# Power.net
KiCad netlist of a schematic drawn in Altium Designer
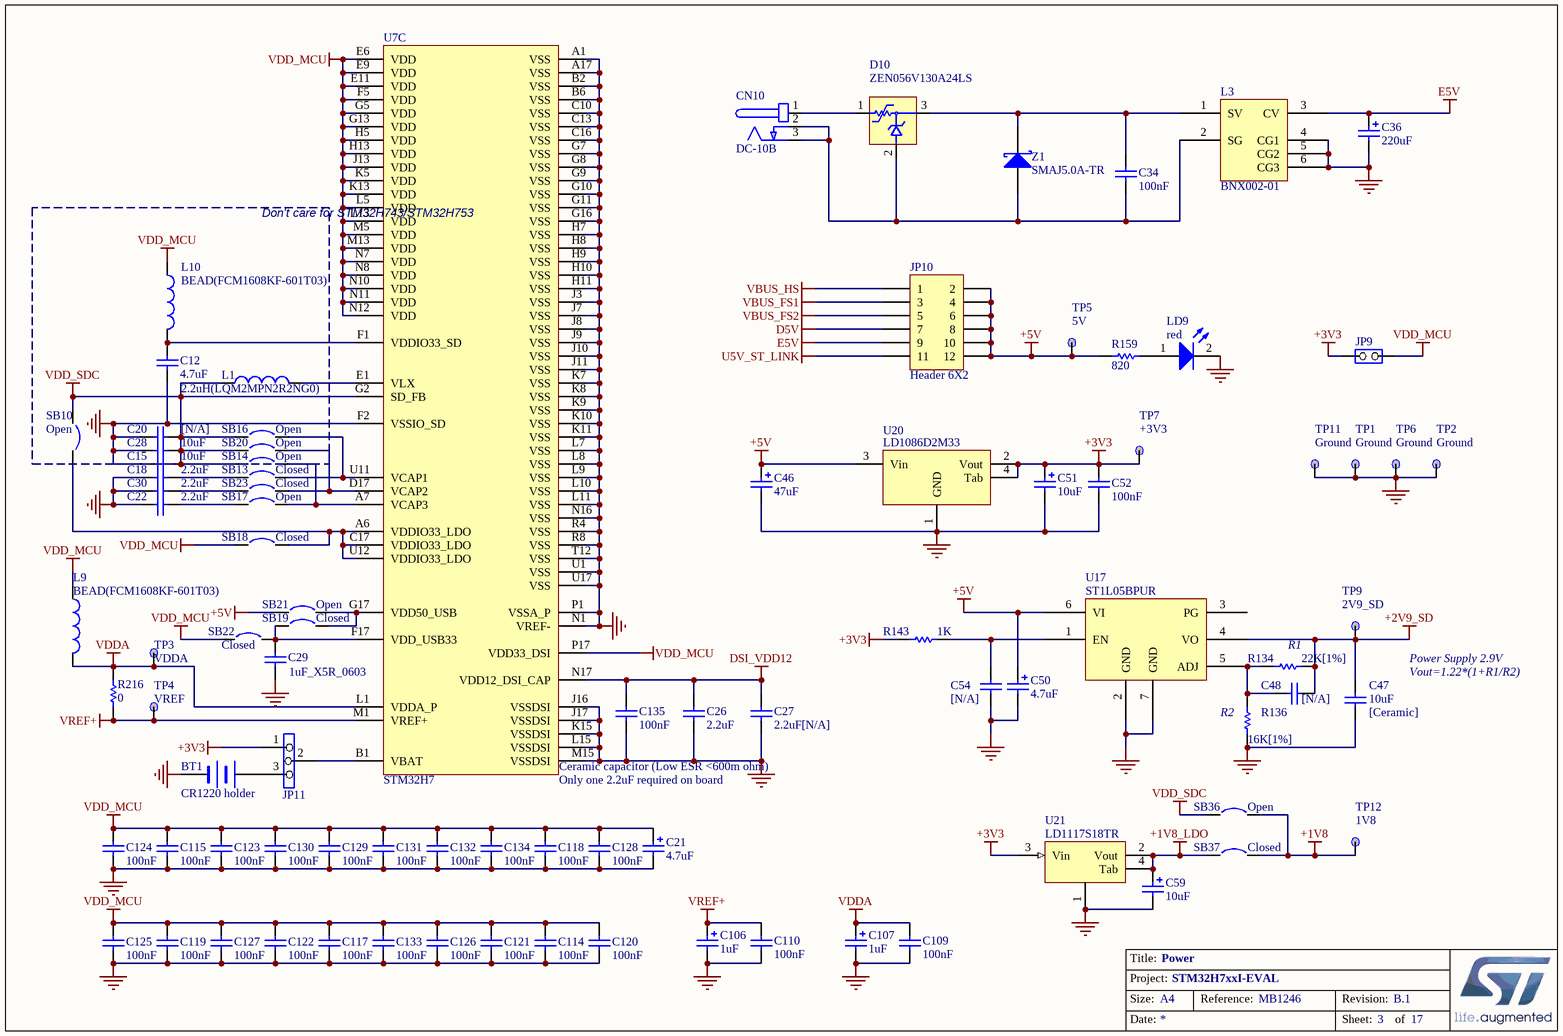
[diagram p0: Power.SchDoc]

(export (version "E")
  (design (tool "Eeschema 10.0.6"))
  (components
    (comp (ref "BT1")
      (value "CR1220 holder")
      (footprint "BAT_2SM_CR1220")
      (description "Battery")
      (libsource (lib "*") (part "BATTERY"))
    )
    (comp (ref "C12")
      (value "4.7uF")
      (footprint "0603C")
      (description "Capacitor")
      (fields (field (name "PUBLISHER") "Altium Limited"))
      (libsource (lib "Miscellaneous Devices") (part "Cap"))
    )
    (comp (ref "C15")
      (value "10uF")
      (footprint "0603C")
      (description "Capacitor")
      (fields (field (name "PUBLISHER") "Altium Limited"))
      (libsource (lib "Miscellaneous Devices") (part "Cap"))
    )
    (comp (ref "C18")
      (value "2.2uF")
      (footprint "0603C")
      (description "Capacitor")
      (fields (field (name "PUBLISHER") "Altium Limited"))
      (libsource (lib "Miscellaneous Devices") (part "Cap"))
    )
    (comp (ref "C20")
      (value "[N/A]")
      (footprint "0603C")
      (description "Capacitor")
      (fields (field (name "PUBLISHER") "Altium Limited"))
      (libsource (lib "Miscellaneous Devices") (part "Cap"))
    )
    (comp (ref "C21")
      (value "4.7uF")
      (footprint "TAN-A")
      (description "Polarized Capacitor (Radial)")
      (fields (field (name "PUBLISHER") "Altium Limited"))
      (libsource (lib "Miscellaneous Devices") (part "Cap Pol1"))
    )
    (comp (ref "C22")
      (value "2.2uF")
      (footprint "0603C")
      (description "Capacitor")
      (fields (field (name "PUBLISHER") "Altium Limited"))
      (libsource (lib "Miscellaneous Devices") (part "Cap"))
    )
    (comp (ref "C26")
      (value "2.2uF")
      (footprint "0402C")
      (description "Capacitor")
      (fields (field (name "PUBLISHER") "Altium Limited"))
      (libsource (lib "Miscellaneous Devices") (part "CAP"))
    )
    (comp (ref "C27")
      (value "2.2uF[N/A]")
      (footprint "1206C")
      (description "Capacitor")
      (fields (field (name "PUBLISHER") "Altium Limited"))
      (libsource (lib "Miscellaneous Devices") (part "Cap"))
    )
    (comp (ref "C28")
      (value "10uF")
      (footprint "0603C")
      (description "Capacitor")
      (fields (field (name "PUBLISHER") "Altium Limited"))
      (libsource (lib "Miscellaneous Devices") (part "Cap"))
    )
    (comp (ref "C29")
      (value "1uF_X5R_0603")
      (footprint "0603C")
      (description "0603  X5R 1µF")
      (fields (field (name "TOLERANCE") "10%"))
      (libsource (lib "MB963_1") (part "CAP SMD 0603  X5R 1µF 25V 10%"))
    )
    (comp (ref "C30")
      (value "2.2uF")
      (footprint "0603C")
      (description "Capacitor")
      (fields (field (name "PUBLISHER") "Altium Limited"))
      (libsource (lib "Miscellaneous Devices") (part "Cap"))
    )
    (comp (ref "C34")
      (value "100nF")
      (footprint "0603C")
      (description "Capacitor")
      (fields (field (name "PUBLISHER") "Altium Limited"))
      (libsource (lib "Miscellaneous Devices") (part "CAP"))
    )
    (comp (ref "C36")
      (value "220uF")
      (footprint "c310m-6")
      (description "Polarized Capacitor (Radial)")
      (fields (field (name "PUBLISHER") "Altium Limited"))
      (libsource (lib "Miscellaneous Devices") (part "Cap Pol1"))
    )
    (comp (ref "C46")
      (value "47uF")
      (footprint "CAE_5R3X5R3_H5R4")
      (description "Polarized Capacitor (Radial)")
      (fields (field (name "PUBLISHER") "Altium Limited"))
      (libsource (lib "Miscellaneous Devices") (part "Cap Pol1"))
    )
    (comp (ref "C47")
      (value "10uF")
      (footprint "0603C")
      (description "Capacitor")
      (fields (field (name "PUBLISHER") "Altium Limited"))
      (libsource (lib "Miscellaneous Devices") (part "Cap"))
    )
    (comp (ref "C48")
      (value "[N/A]")
      (footprint "0603C")
      (description "Capacitor")
      (fields (field (name "PUBLISHER") "Altium Limited"))
      (libsource (lib "Miscellaneous Devices") (part "Cap"))
    )
    (comp (ref "C50")
      (value "4.7uF")
      (footprint "TAN-A")
      (description "Polarized Capacitor (Radial)")
      (fields (field (name "PUBLISHER") "Altium Limited"))
      (libsource (lib "*") (part "Cap Pol1"))
    )
    (comp (ref "C51")
      (value "10uF")
      (footprint "TAN-A")
      (description "Polarized Capacitor (Radial)")
      (fields (field (name "PUBLISHER") "Altium Limited"))
      (libsource (lib "Miscellaneous Devices") (part "Cap Pol1"))
    )
    (comp (ref "C52")
      (value "100nF")
      (footprint "0603C")
      (description "Capacitor")
      (fields (field (name "PUBLISHER") "Altium Limited"))
      (libsource (lib "Miscellaneous Devices") (part "Cap"))
    )
    (comp (ref "C54")
      (value "[N/A]")
      (footprint "0603C")
      (description "Capacitor")
      (fields (field (name "PUBLISHER") "Altium Limited"))
      (libsource (lib "Miscellaneous Devices") (part "Cap"))
    )
    (comp (ref "C59")
      (value "10uF")
      (footprint "TAN-A")
      (description "Polarized Capacitor (Radial)")
      (fields (field (name "PUBLISHER") "Altium Limited"))
      (libsource (lib "Miscellaneous Devices") (part "Cap Pol1"))
    )
    (comp (ref "C106")
      (value "1uF")
      (footprint "TAN-A")
      (description "Polarized Capacitor (Radial)")
      (fields (field (name "PUBLISHER") "Altium Limited"))
      (libsource (lib "Miscellaneous Devices") (part "Cap Pol1"))
    )
    (comp (ref "C107")
      (value "1uF")
      (footprint "TAN-A")
      (description "Polarized Capacitor (Radial)")
      (fields (field (name "PUBLISHER") "Altium Limited"))
      (libsource (lib "Miscellaneous Devices") (part "Cap Pol1"))
    )
    (comp (ref "C109")
      (value "100nF")
      (footprint "0402C")
      (description "Capacitor")
      (fields (field (name "PUBLISHER") "Altium Limited"))
      (libsource (lib "Miscellaneous Devices") (part "Cap"))
    )
    (comp (ref "C110")
      (value "100nF")
      (footprint "0402C")
      (description "Capacitor")
      (fields (field (name "PUBLISHER") "Altium Limited"))
      (libsource (lib "Miscellaneous Devices") (part "Cap"))
    )
    (comp (ref "C114")
      (value "100nF")
      (footprint "0402C")
      (description "Capacitor")
      (fields (field (name "PUBLISHER") "Altium Limited"))
      (libsource (lib "Miscellaneous Devices") (part "CAP"))
    )
    (comp (ref "C115")
      (value "100nF")
      (footprint "0402C")
      (description "Capacitor")
      (fields (field (name "PUBLISHER") "Altium Limited"))
      (libsource (lib "Miscellaneous Devices") (part "CAP"))
    )
    (comp (ref "C117")
      (value "100nF")
      (footprint "0402C")
      (description "Capacitor")
      (fields (field (name "PUBLISHER") "Altium Limited"))
      (libsource (lib "Miscellaneous Devices") (part "CAP"))
    )
    (comp (ref "C118")
      (value "100nF")
      (footprint "0402C")
      (description "Capacitor")
      (fields (field (name "PUBLISHER") "Altium Limited"))
      (libsource (lib "Miscellaneous Devices") (part "CAP"))
    )
    (comp (ref "C119")
      (value "100nF")
      (footprint "0402C")
      (description "Capacitor")
      (fields (field (name "PUBLISHER") "Altium Limited"))
      (libsource (lib "Miscellaneous Devices") (part "CAP"))
    )
    (comp (ref "C120")
      (value "100nF")
      (footprint "0402C")
      (description "Capacitor")
      (fields (field (name "PUBLISHER") "Altium Limited"))
      (libsource (lib "Miscellaneous Devices") (part "CAP"))
    )
    (comp (ref "C121")
      (value "100nF")
      (footprint "0402C")
      (description "Capacitor")
      (fields (field (name "PUBLISHER") "Altium Limited"))
      (libsource (lib "Miscellaneous Devices") (part "CAP"))
    )
    (comp (ref "C122")
      (value "100nF")
      (footprint "0402C")
      (description "Capacitor")
      (fields (field (name "PUBLISHER") "Altium Limited"))
      (libsource (lib "Miscellaneous Devices") (part "CAP"))
    )
    (comp (ref "C123")
      (value "100nF")
      (footprint "0402C")
      (description "Capacitor")
      (fields (field (name "PUBLISHER") "Altium Limited"))
      (libsource (lib "Miscellaneous Devices") (part "CAP"))
    )
    (comp (ref "C124")
      (value "100nF")
      (footprint "0402C")
      (description "Capacitor")
      (fields (field (name "PUBLISHER") "Altium Limited"))
      (libsource (lib "Miscellaneous Devices") (part "CAP"))
    )
    (comp (ref "C125")
      (value "100nF")
      (footprint "0402C")
      (description "Capacitor")
      (fields (field (name "PUBLISHER") "Altium Limited"))
      (libsource (lib "Miscellaneous Devices") (part "CAP"))
    )
    (comp (ref "C126")
      (value "100nF")
      (footprint "0402C")
      (description "Capacitor")
      (fields (field (name "PUBLISHER") "Altium Limited"))
      (libsource (lib "Miscellaneous Devices") (part "CAP"))
    )
    (comp (ref "C127")
      (value "100nF")
      (footprint "0402C")
      (description "Capacitor")
      (fields (field (name "PUBLISHER") "Altium Limited"))
      (libsource (lib "Miscellaneous Devices") (part "CAP"))
    )
    (comp (ref "C128")
      (value "100nF")
      (footprint "0402C")
      (description "Capacitor")
      (fields (field (name "PUBLISHER") "Altium Limited"))
      (libsource (lib "Miscellaneous Devices") (part "CAP"))
    )
    (comp (ref "C129")
      (value "100nF")
      (footprint "0402C")
      (description "Capacitor")
      (fields (field (name "PUBLISHER") "Altium Limited"))
      (libsource (lib "Miscellaneous Devices") (part "CAP"))
    )
    (comp (ref "C130")
      (value "100nF")
      (footprint "0402C")
      (description "Capacitor")
      (fields (field (name "PUBLISHER") "Altium Limited"))
      (libsource (lib "Miscellaneous Devices") (part "CAP"))
    )
    (comp (ref "C131")
      (value "100nF")
      (footprint "0402C")
      (description "Capacitor")
      (fields (field (name "PUBLISHER") "Altium Limited"))
      (libsource (lib "Miscellaneous Devices") (part "CAP"))
    )
    (comp (ref "C132")
      (value "100nF")
      (footprint "0402C")
      (description "Capacitor")
      (fields (field (name "PUBLISHER") "Altium Limited"))
      (libsource (lib "Miscellaneous Devices") (part "CAP"))
    )
    (comp (ref "C133")
      (value "100nF")
      (footprint "0402C")
      (description "Capacitor")
      (fields (field (name "PUBLISHER") "Altium Limited"))
      (libsource (lib "Miscellaneous Devices") (part "CAP"))
    )
    (comp (ref "C134")
      (value "100nF")
      (footprint "0402C")
      (description "Capacitor")
      (fields (field (name "PUBLISHER") "Altium Limited"))
      (libsource (lib "Miscellaneous Devices") (part "CAP"))
    )
    (comp (ref "C135")
      (value "100nF")
      (footprint "0402C")
      (description "Capacitor")
      (fields (field (name "PUBLISHER") "Altium Limited"))
      (libsource (lib "Miscellaneous Devices") (part "CAP"))
    )
    (comp (ref "CN10")
      (value "DC-10B")
      (footprint "PWR_JACK_DC10")
      (libsource (lib "STR910_SCHLIB") (part "PJ202A"))
    )
    (comp (ref "D10")
      (value "ZEN056V130A24LS")
      (footprint "TYCO_ZEN056V130A24LS")
      (libsource (lib "STR910_SCHLIB") (part "ZEN056V130A24LS"))
    )
    (comp (ref "JP9") (value "~") (footprint "SIP2") (libsource (lib "*") (part "JP2")))
    (comp (ref "JP10")
      (value "Header 6X2")
      (footprint "HDR_2X6_2R54")
      (description "Header, 6-Pin, Dual row")
      (fields (field (name "PUBLISHER") "Altium Limited"))
      (libsource (lib "mb1045") (part "Header 6X2"))
    )
    (comp (ref "JP11") (value "~") (footprint "SIP3") (libsource (lib "STR910_SCHLIB") (part "Jumper3")))
    (comp (ref "L1")
      (value "2.2uH(LQM2MPN2R2NG0)")
      (footprint "LSM2_VLS2016E_S")
      (description "Inductor")
      (fields (field (name "PUBLISHER") "Altium Limited"))
      (libsource (lib "Miscellaneous Devices") (part "Inductor"))
    )
    (comp (ref "L3")
      (value "BNX002-01")
      (footprint "BNX001")
      (libsource (lib "STR910_SCHLIB") (part "BNX002"))
    )
    (comp (ref "L9")
      (value "BEAD(FCM1608KF-601T03)")
      (footprint "0603L")
      (description "Inductor")
      (fields (field (name "PUBLISHER") "Altium Limited"))
      (libsource (lib "Miscellaneous Devices") (part "Inductor"))
    )
    (comp (ref "L10")
      (value "BEAD(FCM1608KF-601T03)")
      (footprint "0603L")
      (description "Inductor")
      (fields (field (name "PUBLISHER") "Altium Limited"))
      (libsource (lib "Miscellaneous Devices") (part "Inductor"))
    )
    (comp (ref "LD9")
      (value "red")
      (footprint "0603D")
      (description "Typical RED, GREEN, YELLOW, AMBER GaAs LED")
      (fields (field (name "PUBLISHER") "Altium Limited"))
      (libsource (lib "Miscellaneous Devices") (part "LED2"))
    )
    (comp (ref "R134")
      (value "22K[1%]")
      (footprint "0603R")
      (description "Resistor")
      (fields (field (name "PUBLISHER") "Altium Limited"))
      (libsource (lib "Miscellaneous Devices") (part "Res1"))
    )
    (comp (ref "R136")
      (value "16K[1%]")
      (footprint "0603R")
      (description "Resistor")
      (fields (field (name "PUBLISHER") "Altium Limited"))
      (libsource (lib "Miscellaneous Devices") (part "Res1"))
    )
    (comp (ref "R143")
      (value "1K")
      (footprint "0603R")
      (description "Resistor")
      (fields (field (name "PUBLISHER") "Altium Limited"))
      (libsource (lib "Miscellaneous Devices") (part "res1"))
    )
    (comp (ref "R159")
      (value "820")
      (footprint "0603R")
      (description "Resistor")
      (fields (field (name "PUBLISHER") "Altium Limited"))
      (libsource (lib "Miscellaneous Devices") (part "res1"))
    )
    (comp (ref "R216")
      (value "0")
      (footprint "0603R")
      (description "Resistor")
      (fields (field (name "PUBLISHER") "Altium Limited"))
      (libsource (lib "Miscellaneous Devices") (part "Res1"))
    )
    (comp (ref "SB10")
      (value "Open")
      (footprint "SB_0603")
      (description "Circuit Breaker")
      (fields (field (name "PUBLISHER") "Altium Limited"))
      (libsource (lib "MB1165") (part "Circuit Breaker"))
    )
    (comp (ref "SB13")
      (value "Closed")
      (footprint "SB_0603")
      (description "Circuit Breaker")
      (fields (field (name "PUBLISHER") "Altium Limited"))
      (libsource (lib "MB1165") (part "Circuit Breaker_close"))
    )
    (comp (ref "SB14")
      (value "Open")
      (footprint "SB_0603")
      (description "Circuit Breaker")
      (fields (field (name "PUBLISHER") "Altium Limited"))
      (libsource (lib "MB1165") (part "Circuit Breaker"))
    )
    (comp (ref "SB16")
      (value "Open")
      (footprint "SB_0603")
      (description "Circuit Breaker")
      (fields (field (name "PUBLISHER") "Altium Limited"))
      (libsource (lib "MB1165") (part "Circuit Breaker"))
    )
    (comp (ref "SB17")
      (value "Open")
      (footprint "SB_0603")
      (description "Circuit Breaker")
      (fields (field (name "PUBLISHER") "Altium Limited"))
      (libsource (lib "MB1165") (part "Circuit Breaker"))
    )
    (comp (ref "SB18")
      (value "Closed")
      (footprint "SB_0603")
      (description "Circuit Breaker")
      (fields (field (name "PUBLISHER") "Altium Limited"))
      (libsource (lib "MB1165") (part "Circuit Breaker_close"))
    )
    (comp (ref "SB19")
      (value "Closed")
      (footprint "SB_0603")
      (description "Circuit Breaker")
      (fields (field (name "PUBLISHER") "Altium Limited"))
      (libsource (lib "") (part "Circuit Breaker_close_1"))
    )
    (comp (ref "SB20")
      (value "Open")
      (footprint "SB_0603")
      (description "Circuit Breaker")
      (fields (field (name "PUBLISHER") "Altium Limited"))
      (libsource (lib "MB1165") (part "Circuit Breaker"))
    )
    (comp (ref "SB21")
      (value "Open")
      (footprint "SB_0603")
      (description "Circuit Breaker")
      (fields (field (name "PUBLISHER") "Altium Limited"))
      (libsource (lib "MB1165") (part "Circuit Breaker"))
    )
    (comp (ref "SB22")
      (value "Closed")
      (footprint "SB_0603")
      (description "Circuit Breaker")
      (fields (field (name "PUBLISHER") "Altium Limited"))
      (libsource (lib "") (part "Circuit Breaker_close_1"))
    )
    (comp (ref "SB23")
      (value "Closed")
      (footprint "SB_0603")
      (description "Circuit Breaker")
      (fields (field (name "PUBLISHER") "Altium Limited"))
      (libsource (lib "MB1165") (part "Circuit Breaker_close"))
    )
    (comp (ref "SB36")
      (value "Open")
      (footprint "SB_0603")
      (description "Circuit Breaker")
      (fields (field (name "PUBLISHER") "Altium Limited"))
      (libsource (lib "MB1165") (part "Circuit Breaker"))
    )
    (comp (ref "SB37")
      (value "Closed")
      (footprint "SB_0603")
      (description "Circuit Breaker")
      (fields (field (name "PUBLISHER") "Altium Limited"))
      (libsource (lib "") (part "Circuit Breaker_close_1"))
    )
    (comp (ref "TP1") (value "Ground") (footprint "TP") (libsource (lib "*") (part "TP")))
    (comp (ref "TP2") (value "Ground") (footprint "TP") (libsource (lib "*") (part "TP")))
    (comp (ref "TP3") (value "VDDA") (footprint "TP") (libsource (lib "*") (part "TP")))
    (comp (ref "TP4") (value "VREF") (footprint "TP") (libsource (lib "*") (part "TP")))
    (comp (ref "TP5") (value "5V") (footprint "TP") (libsource (lib "*") (part "TP")))
    (comp (ref "TP6") (value "Ground") (footprint "TP") (libsource (lib "*") (part "TP")))
    (comp (ref "TP7") (value "+3V3") (footprint "TP") (libsource (lib "*") (part "TP")))
    (comp (ref "TP9") (value "2V9_SD") (footprint "TP") (libsource (lib "*") (part "TP")))
    (comp (ref "TP11") (value "Ground") (footprint "TP") (libsource (lib "*") (part "TP")))
    (comp (ref "TP12") (value "1V8") (footprint "TP") (libsource (lib "*") (part "TP")))
    (comp (ref "U7")
      (value "STM32H7")
      (footprint "BGA265_0R8_14X14_SKT")
      (libsource (lib "MB1246") (part "STM32H7_TFBGA265"))
    )
    (comp (ref "U17")
      (value "ST1L05BPUR")
      (footprint "DFN6_0R95_3X3")
      (libsource (lib "MB1070") (part "ST1L05"))
    )
    (comp (ref "U20")
      (value "LD1086D2M33")
      (footprint "TO263-3")
      (libsource (lib "mb1045") (part "VOLTREG1"))
    )
    (comp (ref "U21") (value "LD1117S18TR") (footprint "SOT-223") (libsource (lib "mb1045") (part "LD1117")))
    (comp (ref "Z1")
      (value "SMAJ5.0A-TR")
      (footprint "sma")
      (description "Schottky Diode")
      (fields (field (name "PUBLISHER") "Altium Limited"))
      (libsource (lib "Miscellaneous Devices") (part "D Schottky"))
    )
  )
  (nets
    (net (code "1") (name "+1V8") (class "Default")
      (node (ref "SB36") (pin "2") (pinfunction "2_2") (pintype "passive"))
      (node (ref "SB37") (pin "2") (pinfunction "2_2") (pintype "passive"))
      (node (ref "TP12") (pin "1") (pinfunction "1_1") (pintype "passive"))
    )
    (net (code "2") (name "+1V8_LDO") (class "Default")
      (node (ref "C59") (pin "1") (pinfunction "1_1") (pintype "passive"))
      (node (ref "SB37") (pin "1") (pinfunction "1_1") (pintype "passive"))
      (node (ref "U21") (pin "2") (pinfunction "Vout_2") (pintype "power_in"))
      (node (ref "U21") (pin "4") (pinfunction "Tab_4") (pintype "power_in"))
    )
    (net (code "3") (name "+2V9_SD") (class "Default")
      (node (ref "C47") (pin "1") (pinfunction "1_1") (pintype "passive"))
      (node (ref "C48") (pin "2") (pinfunction "2_2") (pintype "passive"))
      (node (ref "R134") (pin "1") (pinfunction "1_1") (pintype "passive"))
      (node (ref "TP9") (pin "1") (pinfunction "1_1") (pintype "passive"))
      (node (ref "U17") (pin "4") (pinfunction "VO_4") (pintype "passive"))
    )
    (net (code "4") (name "+3V3") (class "Default")
      (node (ref "C51") (pin "1") (pinfunction "1_1") (pintype "passive"))
      (node (ref "C52") (pin "1") (pinfunction "1_1") (pintype "passive"))
      (node (ref "JP11") (pin "1") (pintype "passive"))
      (node (ref "JP9") (pin "1") (pinfunction "COMMON_1") (pintype "passive"))
      (node (ref "R143") (pin "2") (pinfunction "2_2") (pintype "passive"))
      (node (ref "TP7") (pin "1") (pinfunction "1_1") (pintype "passive"))
      (node (ref "U20") (pin "2") (pinfunction "Vout_2") (pintype "passive"))
      (node (ref "U20") (pin "4") (pinfunction "Tab_4") (pintype "passive"))
      (node (ref "U21") (pin "3") (pinfunction "Vin_3") (pintype "input"))
    )
    (net (code "5") (name "+5V") (class "Default")
      (node (ref "C46") (pin "1") (pinfunction "1_1") (pintype "passive"))
      (node (ref "C50") (pin "1") (pinfunction "1_1") (pintype "passive"))
      (node (ref "JP10") (pin "10") (pinfunction "10_10") (pintype "passive"))
      (node (ref "JP10") (pin "12") (pinfunction "12_12") (pintype "passive"))
      (node (ref "JP10") (pin "2") (pinfunction "2_2") (pintype "passive"))
      (node (ref "JP10") (pin "4") (pinfunction "4_4") (pintype "passive"))
      (node (ref "JP10") (pin "6") (pinfunction "6_6") (pintype "passive"))
      (node (ref "JP10") (pin "8") (pinfunction "8_8") (pintype "passive"))
      (node (ref "R159") (pin "2") (pinfunction "2_2") (pintype "passive"))
      (node (ref "SB21") (pin "1") (pinfunction "1_1") (pintype "passive"))
      (node (ref "TP5") (pin "1") (pinfunction "1_1") (pintype "passive"))
      (node (ref "U17") (pin "6") (pinfunction "VI_6") (pintype "passive"))
      (node (ref "U20") (pin "3") (pinfunction "Vin_3") (pintype "passive"))
    )
    (net (code "6") (name "D5V") (class "Default")
      (node (ref "JP10") (pin "7") (pinfunction "7_7") (pintype "passive"))
    )
    (net (code "7") (name "DSI_VDD12") (class "Default")
      (node (ref "C135") (pin "1") (pinfunction "1_1") (pintype "passive"))
      (node (ref "C26") (pin "1") (pinfunction "1_1") (pintype "passive"))
      (node (ref "C27") (pin "1") (pinfunction "1_1") (pintype "passive"))
      (node (ref "U7") (pin "N17") (pinfunction "VDD12_DSI_CAP_N17") (pintype "passive"))
    )
    (net (code "8") (name "E5V") (class "Default")
      (node (ref "C36") (pin "1") (pinfunction "1_1") (pintype "passive"))
      (node (ref "JP10") (pin "9") (pinfunction "9_9") (pintype "passive"))
      (node (ref "L3") (pin "3") (pinfunction "CV_3") (pintype "passive"))
    )
    (net (code "9") (name "GND") (class "Default")
      (node (ref "BT1") (pin "2") (pinfunction "-_2") (pintype "passive"))
      (node (ref "C106") (pin "2") (pinfunction "2_2") (pintype "passive"))
      (node (ref "C107") (pin "2") (pinfunction "2_2") (pintype "passive"))
      (node (ref "C109") (pin "1") (pinfunction "1_1") (pintype "passive"))
      (node (ref "C110") (pin "1") (pinfunction "1_1") (pintype "passive"))
      (node (ref "C114") (pin "2") (pinfunction "2_2") (pintype "passive"))
      (node (ref "C115") (pin "2") (pinfunction "2_2") (pintype "passive"))
      (node (ref "C117") (pin "2") (pinfunction "2_2") (pintype "passive"))
      (node (ref "C118") (pin "2") (pinfunction "2_2") (pintype "passive"))
      (node (ref "C119") (pin "2") (pinfunction "2_2") (pintype "passive"))
      (node (ref "C12") (pin "1") (pinfunction "1_1") (pintype "passive"))
      (node (ref "C120") (pin "2") (pinfunction "2_2") (pintype "passive"))
      (node (ref "C121") (pin "2") (pinfunction "2_2") (pintype "passive"))
      (node (ref "C122") (pin "2") (pinfunction "2_2") (pintype "passive"))
      (node (ref "C123") (pin "2") (pinfunction "2_2") (pintype "passive"))
      (node (ref "C124") (pin "2") (pinfunction "2_2") (pintype "passive"))
      (node (ref "C125") (pin "2") (pinfunction "2_2") (pintype "passive"))
      (node (ref "C126") (pin "2") (pinfunction "2_2") (pintype "passive"))
      (node (ref "C127") (pin "2") (pinfunction "2_2") (pintype "passive"))
      (node (ref "C128") (pin "2") (pinfunction "2_2") (pintype "passive"))
      (node (ref "C129") (pin "2") (pinfunction "2_2") (pintype "passive"))
      (node (ref "C130") (pin "2") (pinfunction "2_2") (pintype "passive"))
      (node (ref "C131") (pin "2") (pinfunction "2_2") (pintype "passive"))
      (node (ref "C132") (pin "2") (pinfunction "2_2") (pintype "passive"))
      (node (ref "C133") (pin "2") (pinfunction "2_2") (pintype "passive"))
      (node (ref "C134") (pin "2") (pinfunction "2_2") (pintype "passive"))
      (node (ref "C135") (pin "2") (pinfunction "2_2") (pintype "passive"))
      (node (ref "C15") (pin "1") (pinfunction "1_1") (pintype "passive"))
      (node (ref "C18") (pin "1") (pinfunction "1_1") (pintype "passive"))
      (node (ref "C20") (pin "1") (pinfunction "1_1") (pintype "passive"))
      (node (ref "C21") (pin "2") (pinfunction "2_2") (pintype "passive"))
      (node (ref "C22") (pin "1") (pinfunction "1_1") (pintype "passive"))
      (node (ref "C26") (pin "2") (pinfunction "2_2") (pintype "passive"))
      (node (ref "C27") (pin "2") (pinfunction "2_2") (pintype "passive"))
      (node (ref "C28") (pin "1") (pinfunction "1_1") (pintype "passive"))
      (node (ref "C29") (pin "1") (pinfunction "1_1") (pintype "passive"))
      (node (ref "C30") (pin "1") (pinfunction "1_1") (pintype "passive"))
      (node (ref "C36") (pin "2") (pinfunction "2_2") (pintype "passive"))
      (node (ref "C46") (pin "2") (pinfunction "2_2") (pintype "passive"))
      (node (ref "C47") (pin "2") (pinfunction "2_2") (pintype "passive"))
      (node (ref "C50") (pin "2") (pinfunction "2_2") (pintype "passive"))
      (node (ref "C51") (pin "2") (pinfunction "2_2") (pintype "passive"))
      (node (ref "C52") (pin "2") (pinfunction "2_2") (pintype "passive"))
      (node (ref "C54") (pin "2") (pinfunction "2_2") (pintype "passive"))
      (node (ref "C59") (pin "2") (pinfunction "2_2") (pintype "passive"))
      (node (ref "L3") (pin "4") (pinfunction "CG1_4") (pintype "passive"))
      (node (ref "L3") (pin "5") (pinfunction "CG2_5") (pintype "passive"))
      (node (ref "L3") (pin "6") (pinfunction "CG3_6") (pintype "passive"))
      (node (ref "LD9") (pin "2") (pinfunction "K_2") (pintype "passive"))
      (node (ref "R136") (pin "2") (pinfunction "2_2") (pintype "passive"))
      (node (ref "TP1") (pin "1") (pinfunction "1_1") (pintype "passive"))
      (node (ref "TP11") (pin "1") (pinfunction "1_1") (pintype "passive"))
      (node (ref "TP2") (pin "1") (pinfunction "1_1") (pintype "passive"))
      (node (ref "TP6") (pin "1") (pinfunction "1_1") (pintype "passive"))
      (node (ref "U17") (pin "2") (pinfunction "GND_2") (pintype "passive"))
      (node (ref "U17") (pin "7") (pinfunction "GND_7") (pintype "passive"))
      (node (ref "U20") (pin "1") (pinfunction "GND_1") (pintype "passive"))
      (node (ref "U21") (pin "1") (pintype "passive"))
      (node (ref "U7") (pin "A1") (pinfunction "VSS_A1") (pintype "passive"))
      (node (ref "U7") (pin "A17") (pinfunction "VSS_A17") (pintype "passive"))
      (node (ref "U7") (pin "B2") (pinfunction "VSS_B2") (pintype "passive"))
      (node (ref "U7") (pin "B6") (pinfunction "VSS_B6") (pintype "passive"))
      (node (ref "U7") (pin "C10") (pinfunction "VSS_C10") (pintype "passive"))
      (node (ref "U7") (pin "C13") (pinfunction "VSS_C13") (pintype "passive"))
      (node (ref "U7") (pin "C16") (pinfunction "VSS_C16") (pintype "passive"))
      (node (ref "U7") (pin "F2") (pinfunction "VSSIO_SD_F2") (pintype "passive"))
      (node (ref "U7") (pin "G10") (pinfunction "VSS_G10") (pintype "passive"))
      (node (ref "U7") (pin "G11") (pinfunction "VSS_G11") (pintype "passive"))
      (node (ref "U7") (pin "G16") (pinfunction "VSS_G16") (pintype "passive"))
      (node (ref "U7") (pin "G7") (pinfunction "VSS_G7") (pintype "passive"))
      (node (ref "U7") (pin "G8") (pinfunction "VSS_G8") (pintype "passive"))
      (node (ref "U7") (pin "G9") (pinfunction "VSS_G9") (pintype "passive"))
      (node (ref "U7") (pin "H10") (pinfunction "VSS_H10") (pintype "passive"))
      (node (ref "U7") (pin "H11") (pinfunction "VSS_H11") (pintype "passive"))
      (node (ref "U7") (pin "H7") (pinfunction "VSS_H7") (pintype "passive"))
      (node (ref "U7") (pin "H8") (pinfunction "VSS_H8") (pintype "passive"))
      (node (ref "U7") (pin "H9") (pinfunction "VSS_H9") (pintype "passive"))
      (node (ref "U7") (pin "J10") (pinfunction "VSS_J10") (pintype "passive"))
      (node (ref "U7") (pin "J11") (pinfunction "VSS_J11") (pintype "passive"))
      (node (ref "U7") (pin "J16") (pinfunction "VSSDSI_J16") (pintype "passive"))
      (node (ref "U7") (pin "J17") (pinfunction "VSSDSI_J17") (pintype "passive"))
      (node (ref "U7") (pin "J3") (pinfunction "VSS_J3") (pintype "passive"))
      (node (ref "U7") (pin "J7") (pinfunction "VSS_J7") (pintype "passive"))
      (node (ref "U7") (pin "J8") (pinfunction "VSS_J8") (pintype "passive"))
      (node (ref "U7") (pin "J9") (pinfunction "VSS_J9") (pintype "passive"))
      (node (ref "U7") (pin "K10") (pinfunction "VSS_K10") (pintype "passive"))
      (node (ref "U7") (pin "K11") (pinfunction "VSS_K11") (pintype "passive"))
      (node (ref "U7") (pin "K15") (pinfunction "VSSDSI_K15") (pintype "passive"))
      (node (ref "U7") (pin "K7") (pinfunction "VSS_K7") (pintype "passive"))
      (node (ref "U7") (pin "K8") (pinfunction "VSS_K8") (pintype "passive"))
      (node (ref "U7") (pin "K9") (pinfunction "VSS_K9") (pintype "passive"))
      (node (ref "U7") (pin "L10") (pinfunction "VSS_L10") (pintype "passive"))
      (node (ref "U7") (pin "L11") (pinfunction "VSS_L11") (pintype "passive"))
      (node (ref "U7") (pin "L15") (pinfunction "VSSDSI_L15") (pintype "passive"))
      (node (ref "U7") (pin "L7") (pinfunction "VSS_L7") (pintype "passive"))
      (node (ref "U7") (pin "L8") (pinfunction "VSS_L8") (pintype "passive"))
      (node (ref "U7") (pin "L9") (pinfunction "VSS_L9") (pintype "passive"))
      (node (ref "U7") (pin "M15") (pinfunction "VSSDSI_M15") (pintype "passive"))
      (node (ref "U7") (pin "N1") (pinfunction "VREF-_N1") (pintype "passive"))
      (node (ref "U7") (pin "N16") (pinfunction "VSS_N16") (pintype "passive"))
      (node (ref "U7") (pin "P1") (pinfunction "VSSA_P_P1") (pintype "passive"))
      (node (ref "U7") (pin "R4") (pinfunction "VSS_R4") (pintype "passive"))
      (node (ref "U7") (pin "R8") (pinfunction "VSS_R8") (pintype "passive"))
      (node (ref "U7") (pin "T12") (pinfunction "VSS_T12") (pintype "passive"))
      (node (ref "U7") (pin "U1") (pinfunction "VSS_U1") (pintype "passive"))
      (node (ref "U7") (pin "U17") (pinfunction "VSS_U17") (pintype "passive"))
    )
    (net (code "10") (name "Net-(BT1-+)") (class "Default")
      (node (ref "BT1") (pin "1") (pinfunction "+_1") (pintype "passive"))
      (node (ref "JP11") (pin "3") (pintype "passive"))
    )
    (net (code "11") (name "Net-(C18-Pad2)") (class "Default")
      (node (ref "C18") (pin "2") (pinfunction "2_2") (pintype "passive"))
      (node (ref "SB13") (pin "2") (pinfunction "2_2") (pintype "passive"))
    )
    (net (code "12") (name "Net-(C22-Pad2)") (class "Default")
      (node (ref "C22") (pin "2") (pinfunction "2_2") (pintype "passive"))
      (node (ref "SB17") (pin "1") (pinfunction "1_1") (pintype "passive"))
    )
    (net (code "13") (name "Net-(C30-Pad2)") (class "Default")
      (node (ref "C30") (pin "2") (pinfunction "2_2") (pintype "passive"))
      (node (ref "SB23") (pin "2") (pinfunction "2_2") (pintype "passive"))
    )
    (net (code "14") (name "Net-(CN10-+)") (class "Default")
      (node (ref "CN10") (pin "1") (pinfunction "+_1") (pintype "passive"))
      (node (ref "D10") (pin "1") (pintype "passive"))
    )
    (net (code "15") (name "Net-(L3-SG)") (class "Default")
      (node (ref "C34") (pin "2") (pinfunction "2_2") (pintype "passive"))
      (node (ref "CN10") (pin "2") (pinfunction "GND_2") (pintype "passive"))
      (node (ref "CN10") (pin "3") (pinfunction "GND_3") (pintype "passive"))
      (node (ref "D10") (pin "2") (pintype "passive"))
      (node (ref "L3") (pin "2") (pinfunction "SG_2") (pintype "passive"))
      (node (ref "Z1") (pin "1") (pinfunction "A_1") (pintype "passive"))
    )
    (net (code "16") (name "Net-(L3-SV)") (class "Default")
      (node (ref "C34") (pin "1") (pinfunction "1_1") (pintype "passive"))
      (node (ref "D10") (pin "3") (pintype "passive"))
      (node (ref "L3") (pin "1") (pinfunction "SV_1") (pintype "passive"))
      (node (ref "Z1") (pin "2") (pinfunction "K_2") (pintype "passive"))
    )
    (net (code "17") (name "Net-(LD9-A)") (class "Default")
      (node (ref "LD9") (pin "1") (pinfunction "A_1") (pintype "passive"))
      (node (ref "R159") (pin "1") (pinfunction "1_1") (pintype "passive"))
    )
    (net (code "18") (name "Net-(SB10-Pad2)") (class "Default")
      (node (ref "SB10") (pin "2") (pinfunction "2_2") (pintype "passive"))
      (node (ref "SB18") (pin "1") (pinfunction "1_1") (pintype "passive"))
      (node (ref "U7") (pin "A6") (pinfunction "VDDIO33_LDO_A6") (pintype "passive"))
      (node (ref "U7") (pin "C17") (pinfunction "VDDIO33_LDO_C17") (pintype "passive"))
      (node (ref "U7") (pin "U12") (pinfunction "VDDIO33_LDO_U12") (pintype "passive"))
    )
    (net (code "19") (name "Net-(U7C-VBAT)") (class "Default")
      (node (ref "JP11") (pin "2") (pintype "passive"))
      (node (ref "U7") (pin "B1") (pinfunction "VBAT_B1") (pintype "passive"))
    )
    (net (code "20") (name "Net-(U7C-VCAP1)") (class "Default")
      (node (ref "SB13") (pin "1") (pinfunction "1_1") (pintype "passive"))
      (node (ref "SB16") (pin "2") (pinfunction "2_2") (pintype "passive"))
      (node (ref "U7") (pin "U11") (pinfunction "VCAP1_U11") (pintype "passive"))
    )
    (net (code "21") (name "Net-(U7C-VCAP2)") (class "Default")
      (node (ref "SB20") (pin "2") (pinfunction "2_2") (pintype "passive"))
      (node (ref "SB23") (pin "1") (pinfunction "1_1") (pintype "passive"))
      (node (ref "U7") (pin "D17") (pinfunction "VCAP2_D17") (pintype "passive"))
    )
    (net (code "22") (name "Net-(U7C-VCAP3)") (class "Default")
      (node (ref "SB14") (pin "2") (pinfunction "2_2") (pintype "passive"))
      (node (ref "SB17") (pin "2") (pinfunction "2_2") (pintype "passive"))
      (node (ref "U7") (pin "A7") (pinfunction "VCAP3_A7") (pintype "passive"))
    )
    (net (code "23") (name "Net-(U7C-VDD50_USB)") (class "Default")
      (node (ref "SB19") (pin "2") (pinfunction "2_2") (pintype "passive"))
      (node (ref "SB21") (pin "2") (pinfunction "2_2") (pintype "passive"))
      (node (ref "U7") (pin "G17") (pinfunction "VDD50_USB_G17") (pintype "passive"))
    )
    (net (code "24") (name "Net-(U7C-VDDIO33_SD)") (class "Default")
      (node (ref "C12") (pin "2") (pinfunction "2_2") (pintype "passive"))
      (node (ref "L10") (pin "2") (pinfunction "2_2") (pintype "passive"))
      (node (ref "U7") (pin "F1") (pinfunction "VDDIO33_SD_F1") (pintype "passive"))
    )
    (net (code "25") (name "Net-(U7C-VDD_USB33)") (class "Default")
      (node (ref "C29") (pin "2") (pinfunction "2_2") (pintype "passive"))
      (node (ref "SB19") (pin "1") (pinfunction "1_1") (pintype "passive"))
      (node (ref "SB22") (pin "2") (pinfunction "2_2") (pintype "passive"))
      (node (ref "U7") (pin "F17") (pinfunction "VDD_USB33_F17") (pintype "passive"))
    )
    (net (code "26") (name "Net-(U7C-VLX)") (class "Default")
      (node (ref "L1") (pin "2") (pinfunction "2_2") (pintype "passive"))
      (node (ref "U7") (pin "E1") (pinfunction "VLX_E1") (pintype "passive"))
    )
    (net (code "27") (name "Net-(U17-ADJ)") (class "Default")
      (node (ref "C48") (pin "1") (pinfunction "1_1") (pintype "passive"))
      (node (ref "R134") (pin "2") (pinfunction "2_2") (pintype "passive"))
      (node (ref "R136") (pin "1") (pinfunction "1_1") (pintype "passive"))
      (node (ref "U17") (pin "5") (pinfunction "ADJ_5") (pintype "passive"))
    )
    (net (code "28") (name "Net-(U17-EN)") (class "Default")
      (node (ref "C54") (pin "1") (pinfunction "1_1") (pintype "passive"))
      (node (ref "R143") (pin "1") (pinfunction "1_1") (pintype "passive"))
      (node (ref "U17") (pin "1") (pinfunction "EN_1") (pintype "passive"))
    )
    (net (code "29") (name "U5V_ST_LINK") (class "Default")
      (node (ref "JP10") (pin "11") (pinfunction "11_11") (pintype "passive"))
    )
    (net (code "30") (name "VBUS_FS1") (class "Default")
      (node (ref "JP10") (pin "3") (pinfunction "3_3") (pintype "passive"))
    )
    (net (code "31") (name "VBUS_FS2") (class "Default")
      (node (ref "JP10") (pin "5") (pinfunction "5_5") (pintype "passive"))
    )
    (net (code "32") (name "VBUS_HS") (class "Default")
      (node (ref "JP10") (pin "1") (pinfunction "1_1") (pintype "passive"))
    )
    (net (code "33") (name "VDDA") (class "Default")
      (node (ref "C107") (pin "1") (pinfunction "1_1") (pintype "passive"))
      (node (ref "C109") (pin "2") (pinfunction "2_2") (pintype "passive"))
      (node (ref "L9") (pin "2") (pinfunction "2_2") (pintype "passive"))
      (node (ref "R216") (pin "1") (pinfunction "1_1") (pintype "passive"))
      (node (ref "TP3") (pin "1") (pinfunction "1_1") (pintype "passive"))
      (node (ref "U7") (pin "L1") (pinfunction "VDDA_P_L1") (pintype "passive"))
    )
    (net (code "34") (name "VDD_MCU") (class "Default")
      (node (ref "C114") (pin "1") (pinfunction "1_1") (pintype "passive"))
      (node (ref "C115") (pin "1") (pinfunction "1_1") (pintype "passive"))
      (node (ref "C117") (pin "1") (pinfunction "1_1") (pintype "passive"))
      (node (ref "C118") (pin "1") (pinfunction "1_1") (pintype "passive"))
      (node (ref "C119") (pin "1") (pinfunction "1_1") (pintype "passive"))
      (node (ref "C120") (pin "1") (pinfunction "1_1") (pintype "passive"))
      (node (ref "C121") (pin "1") (pinfunction "1_1") (pintype "passive"))
      (node (ref "C122") (pin "1") (pinfunction "1_1") (pintype "passive"))
      (node (ref "C123") (pin "1") (pinfunction "1_1") (pintype "passive"))
      (node (ref "C124") (pin "1") (pinfunction "1_1") (pintype "passive"))
      (node (ref "C125") (pin "1") (pinfunction "1_1") (pintype "passive"))
      (node (ref "C126") (pin "1") (pinfunction "1_1") (pintype "passive"))
      (node (ref "C127") (pin "1") (pinfunction "1_1") (pintype "passive"))
      (node (ref "C128") (pin "1") (pinfunction "1_1") (pintype "passive"))
      (node (ref "C129") (pin "1") (pinfunction "1_1") (pintype "passive"))
      (node (ref "C130") (pin "1") (pinfunction "1_1") (pintype "passive"))
      (node (ref "C131") (pin "1") (pinfunction "1_1") (pintype "passive"))
      (node (ref "C132") (pin "1") (pinfunction "1_1") (pintype "passive"))
      (node (ref "C133") (pin "1") (pinfunction "1_1") (pintype "passive"))
      (node (ref "C134") (pin "1") (pinfunction "1_1") (pintype "passive"))
      (node (ref "C21") (pin "1") (pinfunction "1_1") (pintype "passive"))
      (node (ref "JP9") (pin "2") (pinfunction "NO_2") (pintype "passive"))
      (node (ref "L10") (pin "1") (pinfunction "1_1") (pintype "passive"))
      (node (ref "L9") (pin "1") (pinfunction "1_1") (pintype "passive"))
      (node (ref "SB18") (pin "2") (pinfunction "2_2") (pintype "passive"))
      (node (ref "SB22") (pin "1") (pinfunction "1_1") (pintype "passive"))
      (node (ref "U7") (pin "E11") (pinfunction "VDD_E11") (pintype "passive"))
      (node (ref "U7") (pin "E6") (pinfunction "VDD_E6") (pintype "passive"))
      (node (ref "U7") (pin "E9") (pinfunction "VDD_E9") (pintype "passive"))
      (node (ref "U7") (pin "F5") (pinfunction "VDD_F5") (pintype "passive"))
      (node (ref "U7") (pin "G13") (pinfunction "VDD_G13") (pintype "passive"))
      (node (ref "U7") (pin "G5") (pinfunction "VDD_G5") (pintype "passive"))
      (node (ref "U7") (pin "H13") (pinfunction "VDD_H13") (pintype "passive"))
      (node (ref "U7") (pin "H5") (pinfunction "VDD_H5") (pintype "passive"))
      (node (ref "U7") (pin "J13") (pinfunction "VDD_J13") (pintype "passive"))
      (node (ref "U7") (pin "K13") (pinfunction "VDD_K13") (pintype "passive"))
      (node (ref "U7") (pin "K5") (pinfunction "VDD_K5") (pintype "passive"))
      (node (ref "U7") (pin "L13") (pinfunction "VDD_L13") (pintype "passive"))
      (node (ref "U7") (pin "L5") (pinfunction "VDD_L5") (pintype "passive"))
      (node (ref "U7") (pin "M13") (pinfunction "VDD_M13") (pintype "passive"))
      (node (ref "U7") (pin "M5") (pinfunction "VDD_M5") (pintype "passive"))
      (node (ref "U7") (pin "N10") (pinfunction "VDD_N10") (pintype "passive"))
      (node (ref "U7") (pin "N11") (pinfunction "VDD_N11") (pintype "passive"))
      (node (ref "U7") (pin "N12") (pinfunction "VDD_N12") (pintype "passive"))
      (node (ref "U7") (pin "N7") (pinfunction "VDD_N7") (pintype "passive"))
      (node (ref "U7") (pin "N8") (pinfunction "VDD_N8") (pintype "passive"))
      (node (ref "U7") (pin "P17") (pinfunction "VDD33_DSI_P17") (pintype "passive"))
    )
    (net (code "35") (name "VDD_SDC") (class "Default")
      (node (ref "C15") (pin "2") (pinfunction "2_2") (pintype "passive"))
      (node (ref "C20") (pin "2") (pinfunction "2_2") (pintype "passive"))
      (node (ref "C28") (pin "2") (pinfunction "2_2") (pintype "passive"))
      (node (ref "L1") (pin "1") (pinfunction "1_1") (pintype "passive"))
      (node (ref "SB10") (pin "1") (pinfunction "1_1") (pintype "passive"))
      (node (ref "SB14") (pin "1") (pinfunction "1_1") (pintype "passive"))
      (node (ref "SB16") (pin "1") (pinfunction "1_1") (pintype "passive"))
      (node (ref "SB20") (pin "1") (pinfunction "1_1") (pintype "passive"))
      (node (ref "SB36") (pin "1") (pinfunction "1_1") (pintype "passive"))
      (node (ref "U7") (pin "G2") (pinfunction "SD_FB_G2") (pintype "passive"))
    )
    (net (code "36") (name "VREF+") (class "Default")
      (node (ref "C106") (pin "1") (pinfunction "1_1") (pintype "passive"))
      (node (ref "C110") (pin "2") (pinfunction "2_2") (pintype "passive"))
      (node (ref "R216") (pin "2") (pinfunction "2_2") (pintype "passive"))
      (node (ref "TP4") (pin "1") (pinfunction "1_1") (pintype "passive"))
      (node (ref "U7") (pin "M1") (pinfunction "VREF+_M1") (pintype "passive"))
    )
    (net (code "37") (name "unconnected-(U17-PG-Pad3)") (class "Default")
      (node (ref "U17") (pin "3") (pinfunction "PG_3") (pintype "passive"))
    )
  )
)
